# MDM_V3_ControlBoard_C.net
KiCad netlist of a schematic drawn in EAGLE
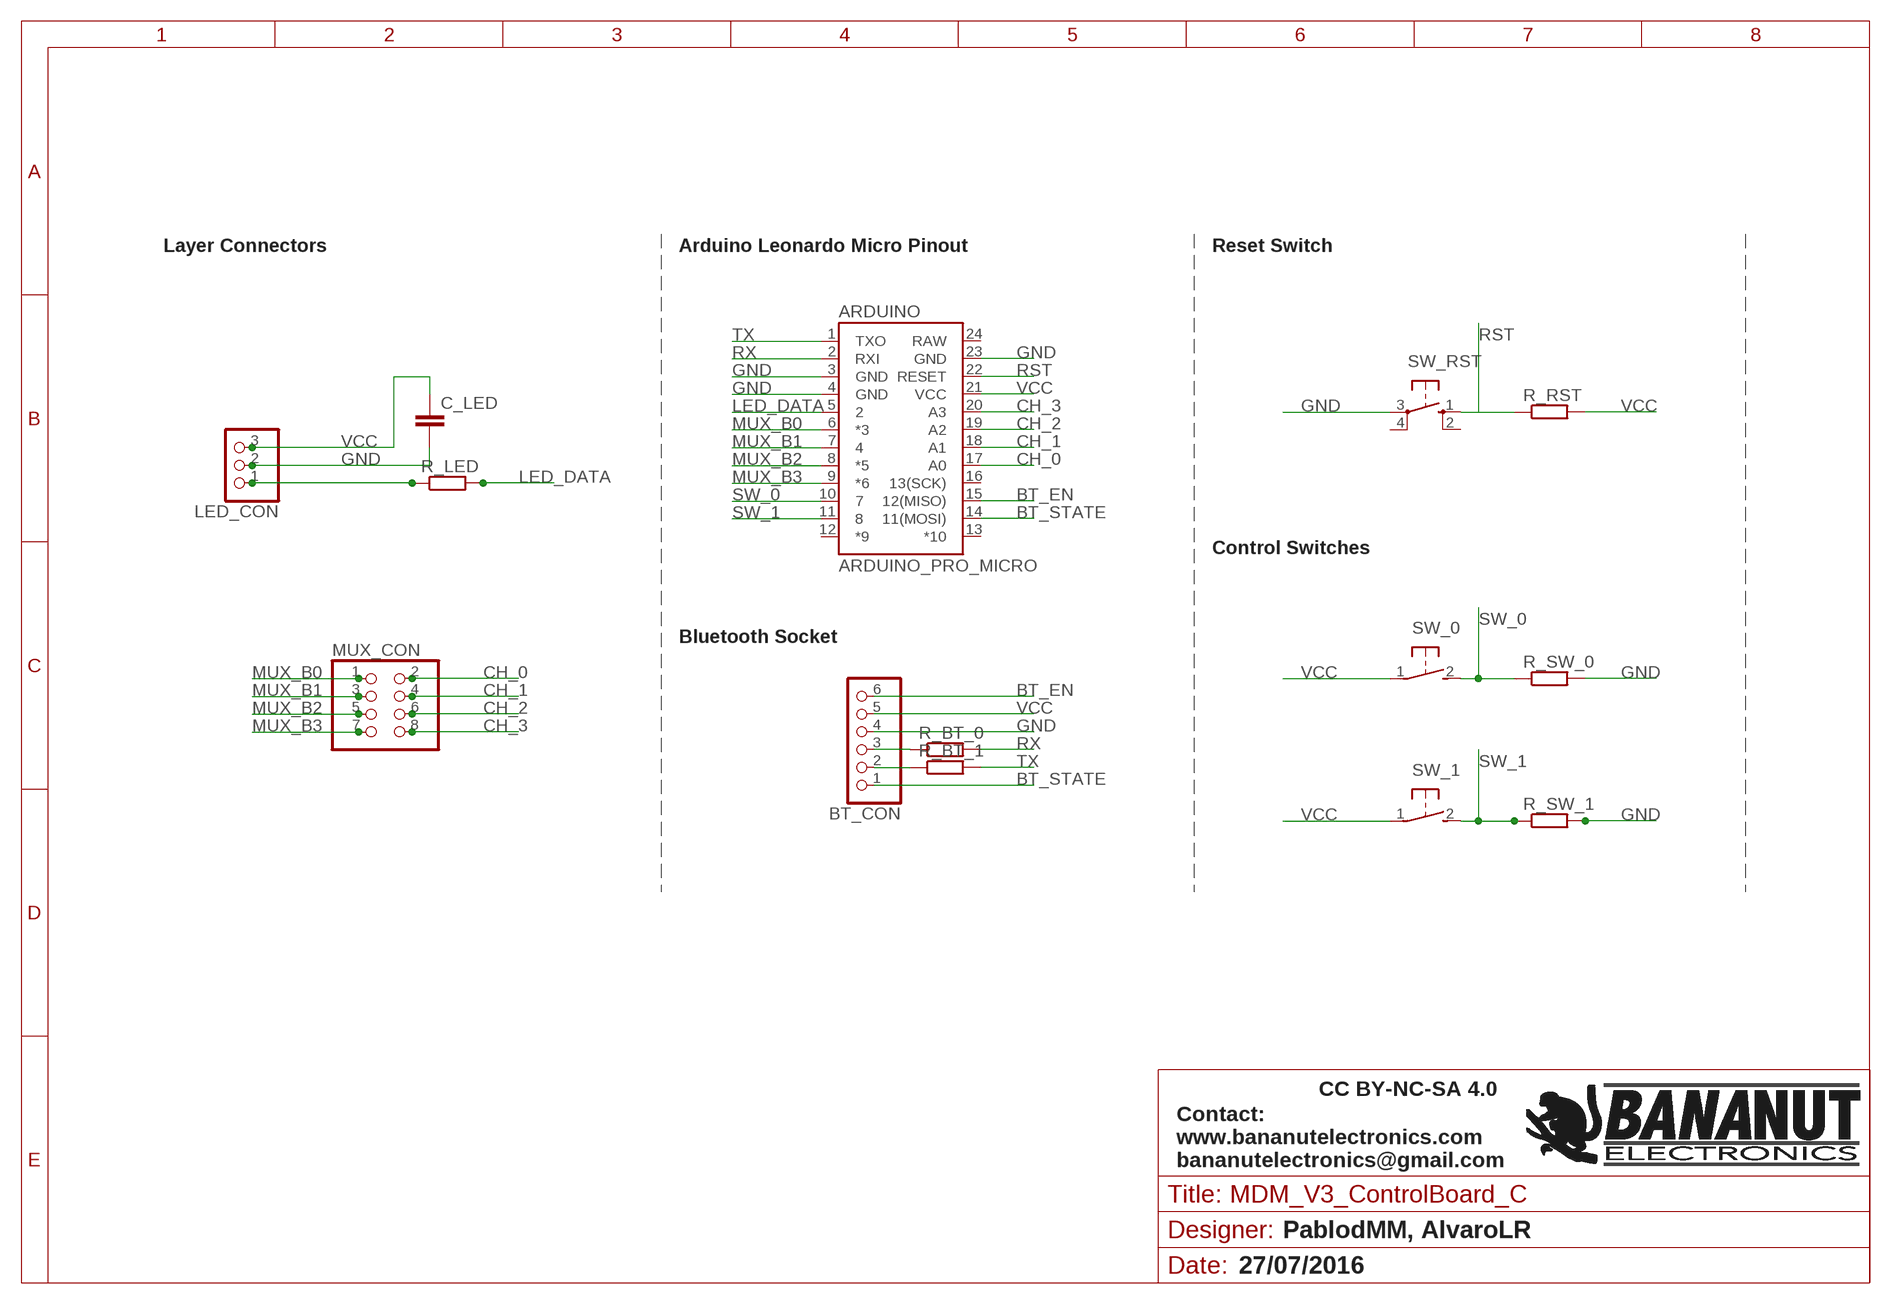
[diagram p0: schematic, sheet 1]

(export (version "E")
  (design (tool "Eeschema 10.0.6"))
  (components
    (comp (ref "ARDUINO")
      (value "ARDUINO_PRO_MICRO")
      (footprint "eagle-import:ARDUINO_PRO_MICRO")
      (libsource (lib "eagle-import") (part "ARDUINO_PRO_MICRO"))
    )
    (comp (ref "BT_CON")
      (value "PINHD-1X6")
      (footprint "eagle-import:1X06")
      (libsource (lib "eagle-import") (part "PINHD-1X6"))
    )
    (comp (ref "C_LED")
      (value "C-EUC1206K")
      (footprint "eagle-import:C1206K")
      (libsource (lib "eagle-import") (part "C-EUC1206K"))
    )
    (comp (ref "LED_CON")
      (value "PINHD-1X3")
      (footprint "eagle-import:1X03")
      (libsource (lib "eagle-import") (part "PINHD-1X3"))
    )
    (comp (ref "MUX_CON")
      (value "PINHD-2X4")
      (footprint "eagle-import:2X04")
      (libsource (lib "eagle-import") (part "PINHD-2X4"))
    )
    (comp (ref "R_BT_0")
      (value "R-EU_M1206")
      (footprint "eagle-import:M1206")
      (libsource (lib "eagle-import") (part "R-EU_M1206"))
    )
    (comp (ref "R_BT_1")
      (value "R-EU_M1206")
      (footprint "eagle-import:M1206")
      (libsource (lib "eagle-import") (part "R-EU_M1206"))
    )
    (comp (ref "R_LED")
      (value "R-EU_M1206")
      (footprint "eagle-import:M1206")
      (libsource (lib "eagle-import") (part "R-EU_M1206"))
    )
    (comp (ref "R_RST")
      (value "R-EU_M1206")
      (footprint "eagle-import:M1206")
      (libsource (lib "eagle-import") (part "R-EU_M1206"))
    )
    (comp (ref "R_SW_0")
      (value "R-EU_M1206")
      (footprint "eagle-import:M1206")
      (libsource (lib "eagle-import") (part "R-EU_M1206"))
    )
    (comp (ref "R_SW_1")
      (value "R-EU_M1206")
      (footprint "eagle-import:M1206")
      (libsource (lib "eagle-import") (part "R-EU_M1206"))
    )
    (comp (ref "SW_0")
      (value "31-XX")
      (footprint "eagle-import:B3F-31XX")
      (fields (field (name "MPN") "B3F-3100"))
      (libsource (lib "eagle-import") (part "31-XX"))
    )
    (comp (ref "SW_1")
      (value "31-XX")
      (footprint "eagle-import:B3F-31XX")
      (fields (field (name "MPN") "B3F-3100"))
      (libsource (lib "eagle-import") (part "31-XX"))
    )
    (comp (ref "SW_RST")
      (value "10-XX")
      (footprint "eagle-import:B3F-10XX")
      (fields (field (name "MPN") "B3F-1000"))
      (libsource (lib "eagle-import") (part "10-XX"))
    )
  )
  (nets
    (net (code "1") (name "/BT_EN") (class "Default")
      (node (ref "ARDUINO") (pin "15") (pinfunction "12(MISO)_15") (pintype "bidirectional"))
      (node (ref "BT_CON") (pin "6") (pinfunction "6_6") (pintype "passive"))
    )
    (net (code "2") (name "/BT_STATE") (class "Default")
      (node (ref "ARDUINO") (pin "14") (pinfunction "11(MOSI)_14") (pintype "bidirectional"))
      (node (ref "BT_CON") (pin "1") (pinfunction "1_1") (pintype "passive"))
    )
    (net (code "3") (name "/CH_0") (class "Default")
      (node (ref "ARDUINO") (pin "17") (pinfunction "A0_17") (pintype "bidirectional"))
      (node (ref "MUX_CON") (pin "2") (pinfunction "2_2") (pintype "passive"))
    )
    (net (code "4") (name "/CH_1") (class "Default")
      (node (ref "ARDUINO") (pin "18") (pinfunction "A1_18") (pintype "bidirectional"))
      (node (ref "MUX_CON") (pin "4") (pinfunction "4_4") (pintype "passive"))
    )
    (net (code "5") (name "/CH_2") (class "Default")
      (node (ref "ARDUINO") (pin "19") (pinfunction "A2_19") (pintype "bidirectional"))
      (node (ref "MUX_CON") (pin "6") (pinfunction "6_6") (pintype "passive"))
    )
    (net (code "6") (name "/CH_3") (class "Default")
      (node (ref "ARDUINO") (pin "20") (pinfunction "A3_20") (pintype "bidirectional"))
      (node (ref "MUX_CON") (pin "8") (pinfunction "8_8") (pintype "passive"))
    )
    (net (code "7") (name "/GND") (class "Default")
      (node (ref "ARDUINO") (pin "23") (pinfunction "GND_23") (pintype "bidirectional"))
      (node (ref "ARDUINO") (pin "3") (pinfunction "GND_3") (pintype "bidirectional"))
      (node (ref "ARDUINO") (pin "4") (pinfunction "GND_4") (pintype "bidirectional"))
      (node (ref "BT_CON") (pin "4") (pinfunction "4_4") (pintype "passive"))
      (node (ref "C_LED") (pin "2") (pinfunction "2_2") (pintype "passive"))
      (node (ref "LED_CON") (pin "2") (pinfunction "2_2") (pintype "passive"))
      (node (ref "R_SW_0") (pin "2") (pinfunction "2_2") (pintype "passive"))
      (node (ref "R_SW_1") (pin "2") (pinfunction "2_2") (pintype "passive"))
      (node (ref "SW_RST") (pin "3") (pinfunction "P_3") (pintype "passive"))
    )
    (net (code "8") (name "/LED_DATA") (class "Default")
      (node (ref "ARDUINO") (pin "5") (pinfunction "2_5") (pintype "bidirectional"))
      (node (ref "R_LED") (pin "2") (pinfunction "2_2") (pintype "passive"))
    )
    (net (code "9") (name "/MUX_B0") (class "Default")
      (node (ref "ARDUINO") (pin "6") (pinfunction "*3_6") (pintype "bidirectional"))
      (node (ref "MUX_CON") (pin "1") (pinfunction "1_1") (pintype "passive"))
    )
    (net (code "10") (name "/MUX_B1") (class "Default")
      (node (ref "ARDUINO") (pin "7") (pinfunction "4_7") (pintype "bidirectional"))
      (node (ref "MUX_CON") (pin "3") (pinfunction "3_3") (pintype "passive"))
    )
    (net (code "11") (name "/MUX_B2") (class "Default")
      (node (ref "ARDUINO") (pin "8") (pinfunction "*5_8") (pintype "bidirectional"))
      (node (ref "MUX_CON") (pin "5") (pinfunction "5_5") (pintype "passive"))
    )
    (net (code "12") (name "/MUX_B3") (class "Default")
      (node (ref "ARDUINO") (pin "9") (pinfunction "*6_9") (pintype "bidirectional"))
      (node (ref "MUX_CON") (pin "7") (pinfunction "7_7") (pintype "passive"))
    )
    (net (code "13") (name "/RST") (class "Default")
      (node (ref "ARDUINO") (pin "22") (pinfunction "RESET_22") (pintype "bidirectional"))
      (node (ref "R_RST") (pin "1") (pinfunction "1_1") (pintype "passive"))
      (node (ref "SW_RST") (pin "1") (pinfunction "S_1") (pintype "passive"))
    )
    (net (code "14") (name "/RX") (class "Default")
      (node (ref "ARDUINO") (pin "2") (pinfunction "RXI_2") (pintype "bidirectional"))
      (node (ref "R_BT_0") (pin "2") (pinfunction "2_2") (pintype "passive"))
    )
    (net (code "15") (name "/SW_0") (class "Default")
      (node (ref "ARDUINO") (pin "10") (pinfunction "7_10") (pintype "bidirectional"))
      (node (ref "R_SW_0") (pin "1") (pinfunction "1_1") (pintype "passive"))
      (node (ref "SW_0") (pin "2") (pinfunction "S_2") (pintype "passive"))
    )
    (net (code "16") (name "/SW_1") (class "Default")
      (node (ref "ARDUINO") (pin "11") (pinfunction "8_11") (pintype "bidirectional"))
      (node (ref "R_SW_1") (pin "1") (pinfunction "1_1") (pintype "passive"))
      (node (ref "SW_1") (pin "2") (pinfunction "S_2") (pintype "passive"))
    )
    (net (code "17") (name "/TX") (class "Default")
      (node (ref "ARDUINO") (pin "1") (pinfunction "TXO_1") (pintype "bidirectional"))
      (node (ref "R_BT_1") (pin "2") (pinfunction "2_2") (pintype "passive"))
    )
    (net (code "18") (name "/VCC") (class "Default")
      (node (ref "ARDUINO") (pin "21") (pinfunction "VCC_21") (pintype "bidirectional"))
      (node (ref "BT_CON") (pin "5") (pinfunction "5_5") (pintype "passive"))
      (node (ref "C_LED") (pin "1") (pinfunction "1_1") (pintype "passive"))
      (node (ref "LED_CON") (pin "3") (pinfunction "3_3") (pintype "passive"))
      (node (ref "R_RST") (pin "2") (pinfunction "2_2") (pintype "passive"))
      (node (ref "SW_0") (pin "1") (pinfunction "P_1") (pintype "passive"))
      (node (ref "SW_1") (pin "1") (pinfunction "P_1") (pintype "passive"))
    )
    (net (code "19") (name "Net-(BT_CON-Pad2)") (class "Default")
      (node (ref "BT_CON") (pin "2") (pinfunction "2_2") (pintype "passive"))
      (node (ref "R_BT_1") (pin "1") (pinfunction "1_1") (pintype "passive"))
    )
    (net (code "20") (name "Net-(BT_CON-Pad3)") (class "Default")
      (node (ref "BT_CON") (pin "3") (pinfunction "3_3") (pintype "passive"))
      (node (ref "R_BT_0") (pin "1") (pinfunction "1_1") (pintype "passive"))
    )
    (net (code "21") (name "Net-(LED_CON-Pad1)") (class "Default")
      (node (ref "LED_CON") (pin "1") (pinfunction "1_1") (pintype "passive"))
      (node (ref "R_LED") (pin "1") (pinfunction "1_1") (pintype "passive"))
    )
    (net (code "22") (name "unconnected-(ARDUINO-*9-Pad12)") (class "Default")
      (node (ref "ARDUINO") (pin "12") (pinfunction "*9_12") (pintype "bidirectional"))
    )
    (net (code "23") (name "unconnected-(ARDUINO-*10-Pad13)") (class "Default")
      (node (ref "ARDUINO") (pin "13") (pinfunction "*10_13") (pintype "bidirectional"))
    )
    (net (code "24") (name "unconnected-(ARDUINO-13(SCK)-Pad16)") (class "Default")
      (node (ref "ARDUINO") (pin "16") (pinfunction "13(SCK)_16") (pintype "bidirectional"))
    )
    (net (code "25") (name "unconnected-(ARDUINO-RAW-Pad24)") (class "Default")
      (node (ref "ARDUINO") (pin "24") (pinfunction "RAW_24") (pintype "bidirectional"))
    )
    (net (code "26") (name "unconnected-(SW_RST-P1-Pad4)") (class "Default")
      (node (ref "SW_RST") (pin "4") (pinfunction "P1_4") (pintype "passive"))
    )
    (net (code "27") (name "unconnected-(SW_RST-S1-Pad2)") (class "Default")
      (node (ref "SW_RST") (pin "2") (pinfunction "S1_2") (pintype "passive"))
    )
  )
)
